# Sheet1.net
KiCad netlist of a schematic drawn in Altium Designer
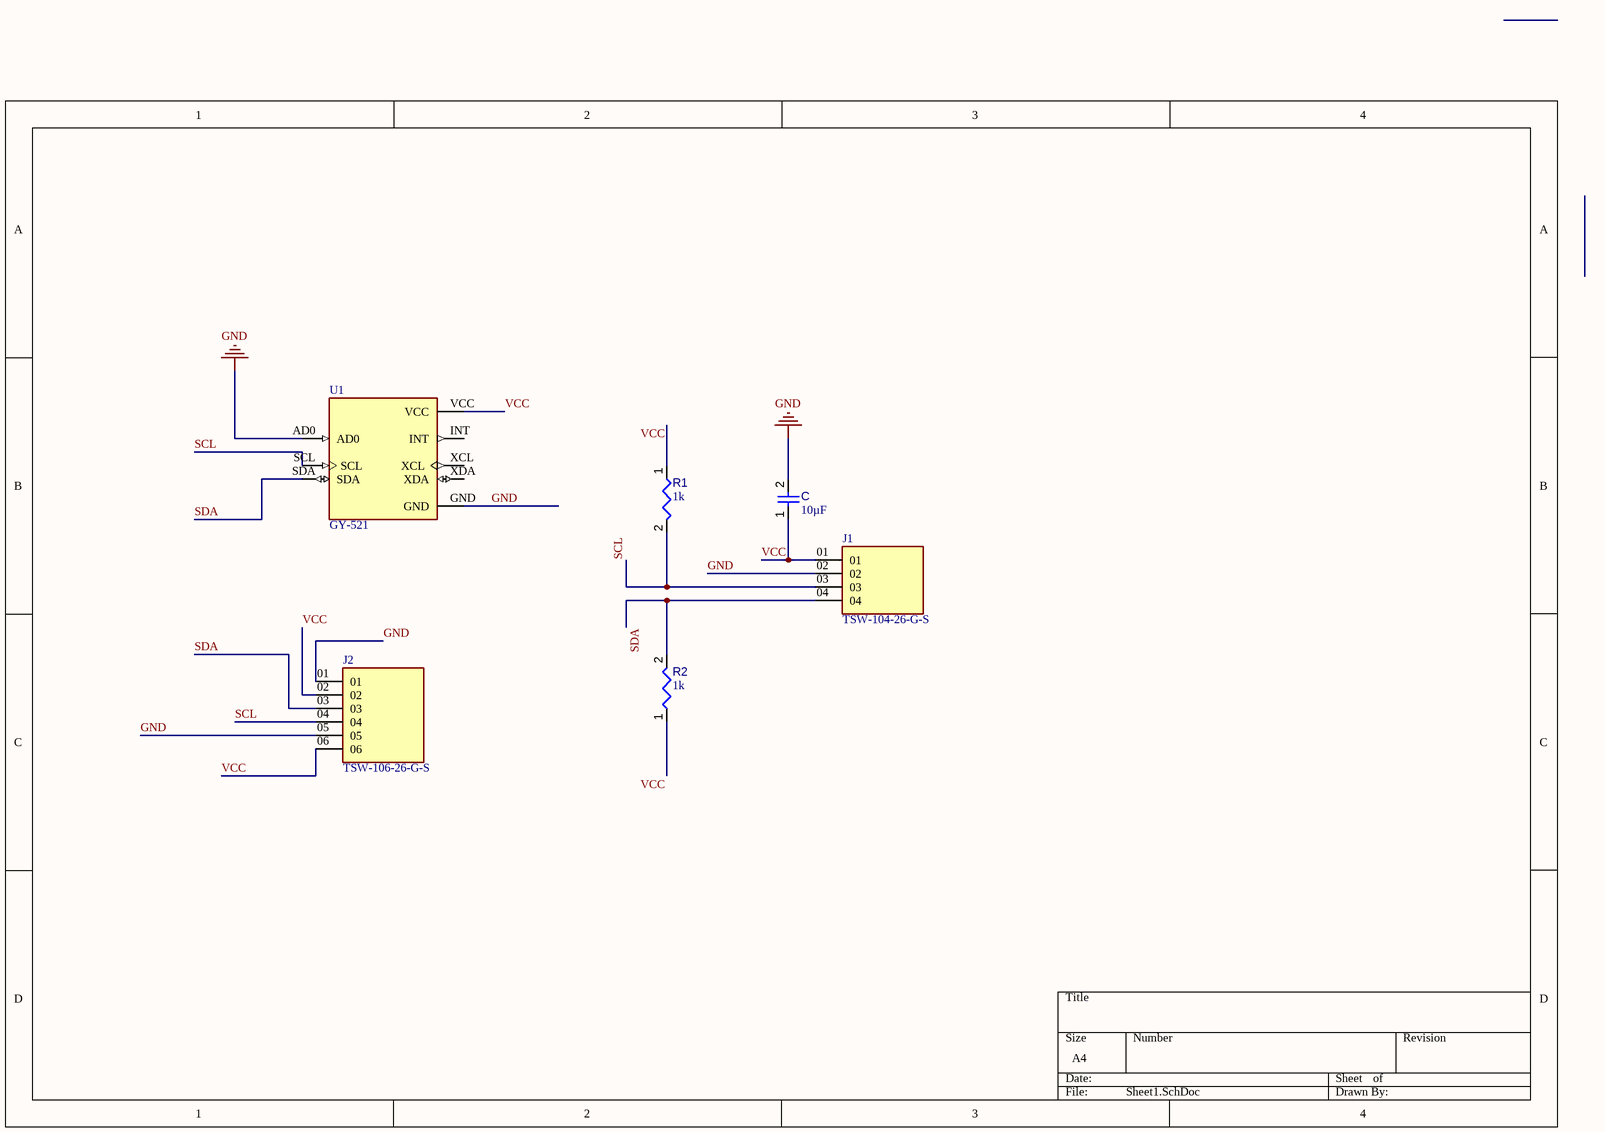
[diagram p0: Sheet1.SchDoc]

(export (version "E")
  (design (tool "Eeschema 10.0.6"))
  (components
    (comp (ref "C")
      (value "10µF")
      (footprint "CAPC3216X180X50NL20T25")
      (description "Chip Capacitor, 10 uF, +/- 10%, 16 V, 1206 (3216 Metric)")
      (fields (field (name "TOLERANCE") "10%") (field (name "Comment") "Capacitor 10 uF +/- 10% 16 V 1206"))
      (libsource (lib "Lachlan Biersteker") (part "CAP-NP-2"))
    )
    (comp (ref "J1")
      (value "TSW-104-26-G-S")
      (footprint "SAMTEC_TSW-104-26-G-S")
      (libsource (lib "Lachlan Biersteker") (part "TSW-104-26-G-S"))
    )
    (comp (ref "J2")
      (value "TSW-106-26-G-S")
      (footprint "SAMTEC_TSW-106-26-G-S")
      (libsource (lib "Lachlan Biersteker") (part "TSW-106-26-G-S"))
    )
    (comp (ref "R1")
      (value "1k")
      (footprint "RESC0402(1005)_L")
      (description "1K 0.063W 5% 0402 (1005 Metric)  SMD")
      (fields (field (name "POWER") "63mW") (field (name "TOLERANCE") "5%"))
      (libsource (lib "Lachlan Biersteker") (part "1KR2J"))
    )
    (comp (ref "R2")
      (value "1k")
      (footprint "RESC0402(1005)_L")
      (description "1K 0.063W 5% 0402 (1005 Metric)  SMD")
      (fields (field (name "POWER") "63mW") (field (name "TOLERANCE") "5%"))
      (libsource (lib "Lachlan Biersteker") (part "1KR2J"))
    )
    (comp (ref "U1")
      (value "GY-521")
      (footprint "MODULE_GY-521")
      (description "Triple Axis Accelerometer Gyro Breakout")
      (fields (field (name "MF") "GODREAM FORDREAM CO., LIMITED"))
      (libsource (lib "Lachlan Biersteker") (part "GY-521"))
    )
  )
  (nets
    (net (code "1") (name "/SCL") (class "Default")
      (node (ref "J1") (pin "03") (pinfunction "03_03") (pintype "passive"))
      (node (ref "J2") (pin "04") (pinfunction "04_04") (pintype "passive"))
      (node (ref "R1") (pin "2") (pinfunction "2_2") (pintype "passive"))
      (node (ref "U1") (pin "SCL") (pinfunction "SCL_SCL") (pintype "input"))
    )
    (net (code "2") (name "/SDA") (class "Default")
      (node (ref "J1") (pin "04") (pinfunction "04_04") (pintype "passive"))
      (node (ref "J2") (pin "03") (pinfunction "03_03") (pintype "passive"))
      (node (ref "R2") (pin "2") (pinfunction "2_2") (pintype "passive"))
      (node (ref "U1") (pin "SDA") (pinfunction "SDA_SDA") (pintype "bidirectional"))
    )
    (net (code "3") (name "/VCC") (class "Default")
      (node (ref "C") (pin "1") (pinfunction "1_1") (pintype "passive"))
      (node (ref "J1") (pin "01") (pinfunction "01_01") (pintype "passive"))
      (node (ref "J2") (pin "02") (pinfunction "02_02") (pintype "passive"))
      (node (ref "J2") (pin "06") (pinfunction "06_06") (pintype "passive"))
      (node (ref "R1") (pin "1") (pinfunction "1_1") (pintype "passive"))
      (node (ref "R2") (pin "1") (pinfunction "1_1") (pintype "passive"))
      (node (ref "U1") (pin "VCC") (pinfunction "VCC_VCC") (pintype "power_in"))
    )
    (net (code "4") (name "GND") (class "Default")
      (node (ref "C") (pin "2") (pinfunction "2_2") (pintype "passive"))
      (node (ref "J1") (pin "02") (pinfunction "02_02") (pintype "passive"))
      (node (ref "J2") (pin "01") (pinfunction "01_01") (pintype "passive"))
      (node (ref "J2") (pin "05") (pinfunction "05_05") (pintype "passive"))
      (node (ref "U1") (pin "AD0") (pinfunction "AD0_AD0") (pintype "input"))
      (node (ref "U1") (pin "GND") (pinfunction "GND_GND") (pintype "power_in"))
    )
    (net (code "5") (name "unconnected-(U1-PadINT)") (class "Default")
      (node (ref "U1") (pin "INT") (pinfunction "INT_INT") (pintype "output"))
    )
    (net (code "6") (name "unconnected-(U1-PadXCL)") (class "Default")
      (node (ref "U1") (pin "XCL") (pinfunction "XCL_XCL") (pintype "output"))
    )
    (net (code "7") (name "unconnected-(U1-PadXDA)") (class "Default")
      (node (ref "U1") (pin "XDA") (pinfunction "XDA_XDA") (pintype "bidirectional"))
    )
  )
)
